# Gyro.net
KiCad netlist of a schematic drawn in EAGLE
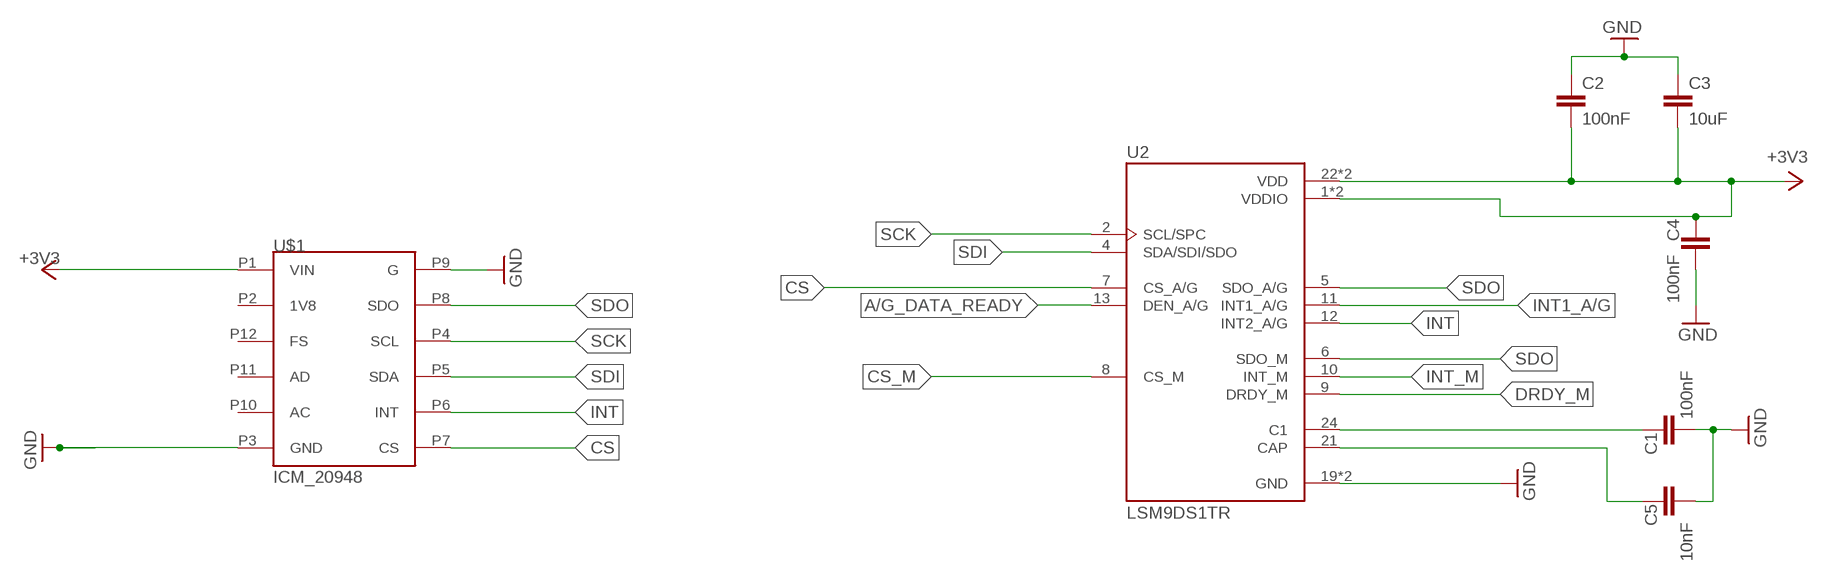
[diagram p0: schematic, sheet 1]

(export (version "E")
  (design (tool "Eeschema 10.0.6"))
  (components
    (comp (ref "C1")
      (value "100nF")
      (footprint "eagle-import:C0805")
      (libsource (lib "eagle-import") (part "C-EUC0805"))
    )
    (comp (ref "C2")
      (value "100nF")
      (footprint "eagle-import:C0805")
      (libsource (lib "eagle-import") (part "C-EUC0805"))
    )
    (comp (ref "C3")
      (value "10uF")
      (footprint "eagle-import:C0805")
      (libsource (lib "eagle-import") (part "C-EUC0805"))
    )
    (comp (ref "C4")
      (value "100nF")
      (footprint "eagle-import:C0805")
      (libsource (lib "eagle-import") (part "C-EUC0805"))
    )
    (comp (ref "C5")
      (value "10nF")
      (footprint "eagle-import:C0805")
      (libsource (lib "eagle-import") (part "C-EUC0805"))
    )
    (comp (ref "U$1")
      (value "ICM_20948")
      (footprint "eagle-import:ICM_20948-F")
      (libsource (lib "eagle-import") (part "ICM_20948"))
    )
    (comp (ref "U2")
      (value "LSM9DS1TR")
      (footprint "eagle-import:PQFN43P300X350X102-24N")
      (fields (field (name "MF") "STMicroelectronics"))
      (libsource (lib "eagle-import") (part "LSM9DS1TR"))
    )
  )
  (nets
    (net (code "1") (name "+3V3") (class "Default")
      (node (ref "C2") (pin "2") (pinfunction "2_2") (pintype "passive"))
      (node (ref "C3") (pin "2") (pinfunction "2_2") (pintype "passive"))
      (node (ref "C4") (pin "2") (pinfunction "2_2") (pintype "passive"))
      (node (ref "U$1") (pin "P1") (pinfunction "VIN_P1") (pintype "bidirectional"))
      (node (ref "U2") (pin "1") (pinfunction "VDDIO_1") (pintype "power_in"))
      (node (ref "U2") (pin "22") (pinfunction "VDD_22") (pintype "power_in"))
      (node (ref "U2") (pin "23") (pinfunction "VDD_23") (pintype "power_in"))
      (node (ref "U2") (pin "3") (pinfunction "VDDIO_3") (pintype "power_in"))
    )
    (net (code "2") (name "A{slash}G_DATA_READY") (class "Default")
      (node (ref "U2") (pin "13") (pinfunction "DEN_A/G_13") (pintype "input"))
    )
    (net (code "3") (name "CS") (class "Default")
      (node (ref "U$1") (pin "P7") (pinfunction "CS_P7") (pintype "bidirectional"))
      (node (ref "U2") (pin "7") (pinfunction "CS_A/G_7") (pintype "input"))
    )
    (net (code "4") (name "CS_M") (class "Default")
      (node (ref "U2") (pin "8") (pinfunction "CS_M_8") (pintype "input"))
    )
    (net (code "5") (name "DRDY_M") (class "Default")
      (node (ref "U2") (pin "9") (pinfunction "DRDY_M_9") (pintype "output"))
    )
    (net (code "6") (name "GND") (class "Default")
      (node (ref "C1") (pin "2") (pinfunction "2_2") (pintype "passive"))
      (node (ref "C2") (pin "1") (pinfunction "1_1") (pintype "passive"))
      (node (ref "C3") (pin "1") (pinfunction "1_1") (pintype "passive"))
      (node (ref "C4") (pin "1") (pinfunction "1_1") (pintype "passive"))
      (node (ref "C5") (pin "2") (pinfunction "2_2") (pintype "passive"))
      (node (ref "U$1") (pin "P3") (pinfunction "GND_P3") (pintype "bidirectional"))
      (node (ref "U$1") (pin "P9") (pinfunction "G_P9") (pintype "bidirectional"))
      (node (ref "U2") (pin "19") (pinfunction "GND_19") (pintype "power_in"))
      (node (ref "U2") (pin "20") (pinfunction "GND_20") (pintype "power_in"))
    )
    (net (code "7") (name "INT") (class "Default")
      (node (ref "U$1") (pin "P6") (pinfunction "INT_P6") (pintype "bidirectional"))
      (node (ref "U2") (pin "12") (pinfunction "INT2_A/G_12") (pintype "output"))
    )
    (net (code "8") (name "INT1_A{slash}G") (class "Default")
      (node (ref "U2") (pin "11") (pinfunction "INT1_A/G_11") (pintype "output"))
    )
    (net (code "9") (name "INT_M") (class "Default")
      (node (ref "U2") (pin "10") (pinfunction "INT_M_10") (pintype "output"))
    )
    (net (code "10") (name "Net-(U2-C1)") (class "Default")
      (node (ref "C1") (pin "1") (pinfunction "1_1") (pintype "passive"))
      (node (ref "U2") (pin "24") (pinfunction "C1_24") (pintype "passive"))
    )
    (net (code "11") (name "Net-(U2-CAP)") (class "Default")
      (node (ref "C5") (pin "1") (pinfunction "1_1") (pintype "passive"))
      (node (ref "U2") (pin "21") (pinfunction "CAP_21") (pintype "passive"))
    )
    (net (code "12") (name "SCK") (class "Default")
      (node (ref "U$1") (pin "P4") (pinfunction "SCL_P4") (pintype "bidirectional"))
      (node (ref "U2") (pin "2") (pinfunction "SCL/SPC_2") (pintype "input"))
    )
    (net (code "13") (name "SDI") (class "Default")
      (node (ref "U$1") (pin "P5") (pinfunction "SDA_P5") (pintype "bidirectional"))
      (node (ref "U2") (pin "4") (pinfunction "SDA/SDI/SDO_4") (pintype "bidirectional"))
    )
    (net (code "14") (name "SDO") (class "Default")
      (node (ref "U$1") (pin "P8") (pinfunction "SDO_P8") (pintype "bidirectional"))
      (node (ref "U2") (pin "5") (pinfunction "SDO_A/G_5") (pintype "output"))
      (node (ref "U2") (pin "6") (pinfunction "SDO_M_6") (pintype "output"))
    )
    (net (code "15") (name "unconnected-(U$1-1V8-PadP2)") (class "Default")
      (node (ref "U$1") (pin "P2") (pinfunction "1V8_P2") (pintype "bidirectional"))
    )
    (net (code "16") (name "unconnected-(U$1-AC-PadP10)") (class "Default")
      (node (ref "U$1") (pin "P10") (pinfunction "AC_P10") (pintype "bidirectional"))
    )
    (net (code "17") (name "unconnected-(U$1-AD-PadP11)") (class "Default")
      (node (ref "U$1") (pin "P11") (pinfunction "AD_P11") (pintype "bidirectional"))
    )
    (net (code "18") (name "unconnected-(U$1-FS-PadP12)") (class "Default")
      (node (ref "U$1") (pin "P12") (pinfunction "FS_P12") (pintype "bidirectional"))
    )
  )
)
